# schematics.net
KiCad netlist of a schematic drawn in EasyEDA
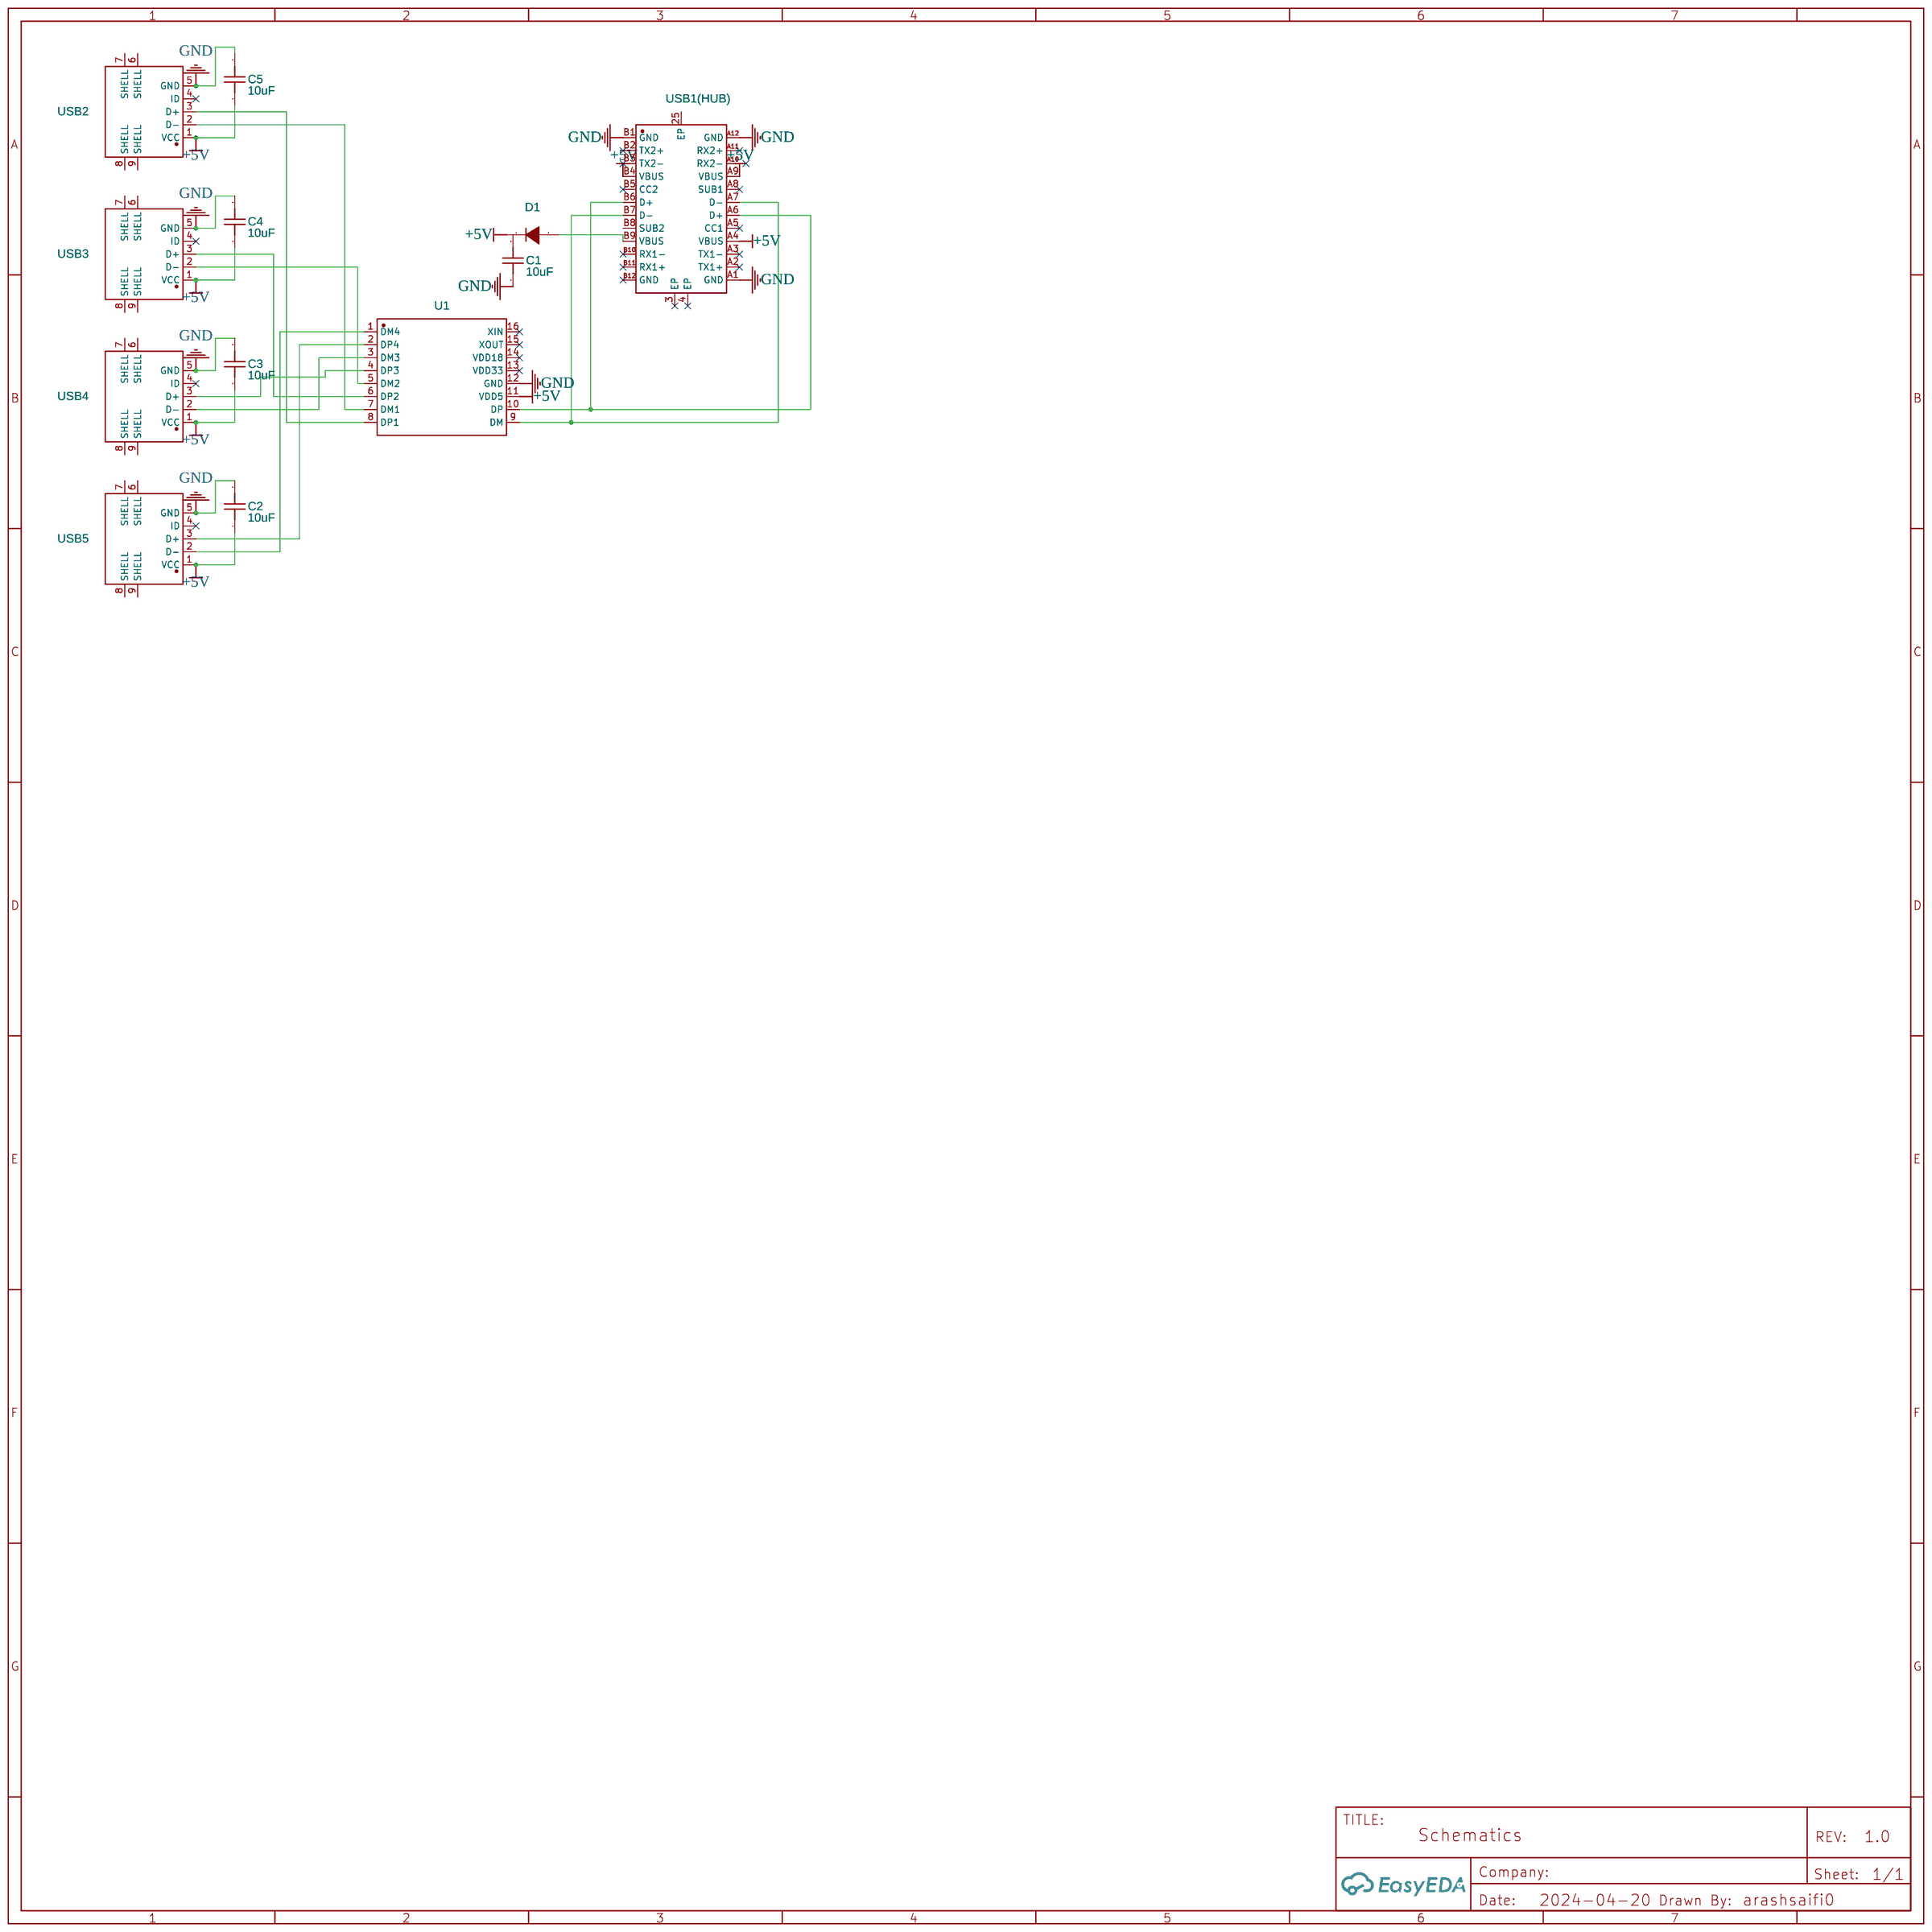
[diagram p0: schematic sheet]

(export (version "E")
  (design (tool "Eeschema 10.0.6"))
  (components
    (comp (ref "C1")
      (value "10uF")
      (fields
        (field (name "Manufacturer Part") "CL10A106KP8NNNC")
        (field (name "Manufacturer") "SAMSUNG(三星)")
      )
      (libsource (lib "") (part "CL10A106KP8NNNC"))
    )
    (comp (ref "C2")
      (value "10uF")
      (fields
        (field (name "Manufacturer Part") "CL10A106KP8NNNC")
        (field (name "Manufacturer") "SAMSUNG(三星)")
      )
      (libsource (lib "") (part "CL10A106KP8NNNC"))
    )
    (comp (ref "C3")
      (value "10uF")
      (fields
        (field (name "Manufacturer Part") "CL10A106KP8NNNC")
        (field (name "Manufacturer") "SAMSUNG(三星)")
      )
      (libsource (lib "") (part "CL10A106KP8NNNC"))
    )
    (comp (ref "C4")
      (value "10uF")
      (fields
        (field (name "Manufacturer Part") "CL10A106KP8NNNC")
        (field (name "Manufacturer") "SAMSUNG(三星)")
      )
      (libsource (lib "") (part "CL10A106KP8NNNC"))
    )
    (comp (ref "C5")
      (value "10uF")
      (fields
        (field (name "Manufacturer Part") "CL10A106KP8NNNC")
        (field (name "Manufacturer") "SAMSUNG(三星)")
      )
      (libsource (lib "") (part "CL10A106KP8NNNC"))
    )
    (comp (ref "D1")
      (value "NSR0320MW2T1G")
      (fields (field (name "Manufacturer") "onsemi(安森美)"))
      (libsource (lib "") (part "NSR0320MW2T1G"))
    )
    (comp (ref "U1")
      (value "SL2.1A")
      (fields (field (name "Manufacturer") "CoreChips(和芯润德)"))
      (libsource (lib "") (part "SL2.1A"))
    )
    (comp (ref "USB1(HUB)")
      (value "TYPE-C 24P QT")
      (fields (field (name "Manufacturer") "SHOU HAN(首韩)"))
      (libsource (lib "") (part "TYPE-C 24P QT"))
    )
    (comp (ref "USB2")
      (value "U224-051N-3GRA035")
      (fields (field (name "Manufacturer") "XKB Connectivity(中国星坤)"))
      (libsource (lib "") (part "U224-051N-3GRA035"))
    )
    (comp (ref "USB3")
      (value "U224-051N-3GRA035")
      (fields (field (name "Manufacturer") "XKB Connectivity(中国星坤)"))
      (libsource (lib "") (part "U224-051N-3GRA035"))
    )
    (comp (ref "USB4")
      (value "U224-051N-3GRA035")
      (fields (field (name "Manufacturer") "XKB Connectivity(中国星坤)"))
      (libsource (lib "") (part "U224-051N-3GRA035"))
    )
    (comp (ref "USB5")
      (value "U224-051N-3GRA035")
      (fields (field (name "Manufacturer") "XKB Connectivity(中国星坤)"))
      (libsource (lib "") (part "U224-051N-3GRA035"))
    )
  )
  (nets
    (net (code "1") (name "+5V") (class "Default")
      (node (ref "C2") (pin "1") (pinfunction "1_1") (pintype "unspecified"))
      (node (ref "C3") (pin "1") (pinfunction "1_1") (pintype "unspecified"))
      (node (ref "C4") (pin "1") (pinfunction "1_1") (pintype "unspecified"))
      (node (ref "C5") (pin "1") (pinfunction "1_1") (pintype "unspecified"))
      (node (ref "D1") (pin "1") (pinfunction "C_1") (pintype "unspecified"))
      (node (ref "U1") (pin "11") (pinfunction "VDD5_11") (pintype "unspecified"))
      (node (ref "USB1(HUB)") (pin "A4") (pinfunction "VBUS_A4") (pintype "unspecified"))
      (node (ref "USB1(HUB)") (pin "A9") (pinfunction "VBUS_A9") (pintype "unspecified"))
      (node (ref "USB1(HUB)") (pin "B4") (pinfunction "VBUS_B4") (pintype "unspecified"))
      (node (ref "USB2") (pin "1") (pinfunction "VCC_1") (pintype "unspecified"))
      (node (ref "USB3") (pin "1") (pinfunction "VCC_1") (pintype "unspecified"))
      (node (ref "USB4") (pin "1") (pinfunction "VCC_1") (pintype "unspecified"))
      (node (ref "USB5") (pin "1") (pinfunction "VCC_1") (pintype "unspecified"))
    )
    (net (code "2") (name "GND") (class "Default")
      (node (ref "C1") (pin "1") (pinfunction "1_1") (pintype "unspecified"))
      (node (ref "C2") (pin "2") (pinfunction "2_2") (pintype "unspecified"))
      (node (ref "C3") (pin "2") (pinfunction "2_2") (pintype "unspecified"))
      (node (ref "C4") (pin "2") (pinfunction "2_2") (pintype "unspecified"))
      (node (ref "C5") (pin "2") (pinfunction "2_2") (pintype "unspecified"))
      (node (ref "U1") (pin "12") (pinfunction "GND_12") (pintype "unspecified"))
      (node (ref "USB1(HUB)") (pin "A1") (pinfunction "GND_A1") (pintype "unspecified"))
      (node (ref "USB1(HUB)") (pin "A12") (pinfunction "GND_A12") (pintype "unspecified"))
      (node (ref "USB1(HUB)") (pin "B1") (pinfunction "GND_B1") (pintype "unspecified"))
      (node (ref "USB2") (pin "5") (pinfunction "GND_5") (pintype "unspecified"))
      (node (ref "USB3") (pin "5") (pinfunction "GND_5") (pintype "unspecified"))
      (node (ref "USB4") (pin "5") (pinfunction "GND_5") (pintype "unspecified"))
      (node (ref "USB5") (pin "5") (pinfunction "GND_5") (pintype "unspecified"))
    )
    (net (code "3") (name "Net-(D1-A)") (class "Default")
      (node (ref "D1") (pin "2") (pinfunction "A_2") (pintype "unspecified"))
      (node (ref "USB1(HUB)") (pin "B9") (pinfunction "VBUS_B9") (pintype "unspecified"))
    )
    (net (code "4") (name "Net-(U1-DM)") (class "Default")
      (node (ref "U1") (pin "9") (pinfunction "DM_9") (pintype "unspecified"))
      (node (ref "USB1(HUB)") (pin "A7") (pinfunction "D-_A7") (pintype "unspecified"))
      (node (ref "USB1(HUB)") (pin "B7") (pinfunction "D-_B7") (pintype "unspecified"))
    )
    (net (code "5") (name "Net-(U1-DM1)") (class "Default")
      (node (ref "U1") (pin "7") (pinfunction "DM1_7") (pintype "unspecified"))
      (node (ref "USB2") (pin "2") (pinfunction "D-_2") (pintype "unspecified"))
    )
    (net (code "6") (name "Net-(U1-DM2)") (class "Default")
      (node (ref "U1") (pin "5") (pinfunction "DM2_5") (pintype "unspecified"))
      (node (ref "USB3") (pin "2") (pinfunction "D-_2") (pintype "unspecified"))
    )
    (net (code "7") (name "Net-(U1-DM3)") (class "Default")
      (node (ref "U1") (pin "3") (pinfunction "DM3_3") (pintype "unspecified"))
      (node (ref "USB4") (pin "2") (pinfunction "D-_2") (pintype "unspecified"))
    )
    (net (code "8") (name "Net-(U1-DM4)") (class "Default")
      (node (ref "U1") (pin "1") (pinfunction "DM4_1") (pintype "unspecified"))
      (node (ref "USB5") (pin "2") (pinfunction "D-_2") (pintype "unspecified"))
    )
    (net (code "9") (name "Net-(U1-DP)") (class "Default")
      (node (ref "U1") (pin "10") (pinfunction "DP_10") (pintype "unspecified"))
      (node (ref "USB1(HUB)") (pin "A6") (pinfunction "D+_A6") (pintype "unspecified"))
      (node (ref "USB1(HUB)") (pin "B6") (pinfunction "D+_B6") (pintype "unspecified"))
    )
    (net (code "10") (name "Net-(U1-DP1)") (class "Default")
      (node (ref "U1") (pin "8") (pinfunction "DP1_8") (pintype "unspecified"))
      (node (ref "USB2") (pin "3") (pinfunction "D+_3") (pintype "unspecified"))
    )
    (net (code "11") (name "Net-(U1-DP2)") (class "Default")
      (node (ref "U1") (pin "6") (pinfunction "DP2_6") (pintype "unspecified"))
      (node (ref "USB3") (pin "3") (pinfunction "D+_3") (pintype "unspecified"))
    )
    (net (code "12") (name "Net-(U1-DP3)") (class "Default")
      (node (ref "U1") (pin "4") (pinfunction "DP3_4") (pintype "unspecified"))
      (node (ref "USB4") (pin "3") (pinfunction "D+_3") (pintype "unspecified"))
    )
    (net (code "13") (name "Net-(U1-DP4)") (class "Default")
      (node (ref "U1") (pin "2") (pinfunction "DP4_2") (pintype "unspecified"))
      (node (ref "USB5") (pin "3") (pinfunction "D+_3") (pintype "unspecified"))
    )
    (net (code "14") (name "unconnected-(C1-Pad2)") (class "Default")
      (node (ref "C1") (pin "2") (pinfunction "2_2") (pintype "unspecified"))
    )
    (net (code "15") (name "unconnected-(U1-VDD18-Pad14)") (class "Default")
      (node (ref "U1") (pin "14") (pinfunction "VDD18_14") (pintype "unspecified+no_connect"))
    )
    (net (code "16") (name "unconnected-(U1-VDD33-Pad13)") (class "Default")
      (node (ref "U1") (pin "13") (pinfunction "VDD33_13") (pintype "unspecified+no_connect"))
    )
    (net (code "17") (name "unconnected-(U1-XIN-Pad16)") (class "Default")
      (node (ref "U1") (pin "16") (pinfunction "XIN_16") (pintype "unspecified+no_connect"))
    )
    (net (code "18") (name "unconnected-(U1-XOUT-Pad15)") (class "Default")
      (node (ref "U1") (pin "15") (pinfunction "XOUT_15") (pintype "unspecified+no_connect"))
    )
    (net (code "19") (name "unconnected-(USB1(HUB)-CC1-PadA5)") (class "Default")
      (node (ref "USB1(HUB)") (pin "A5") (pinfunction "CC1_A5") (pintype "unspecified+no_connect"))
    )
    (net (code "20") (name "unconnected-(USB1(HUB)-CC2-PadB5)") (class "Default")
      (node (ref "USB1(HUB)") (pin "B5") (pinfunction "CC2_B5") (pintype "unspecified+no_connect"))
    )
    (net (code "21") (name "unconnected-(USB1(HUB)-EP-Pad3)") (class "Default")
      (node (ref "USB1(HUB)") (pin "3") (pinfunction "EP_3") (pintype "unspecified+no_connect"))
    )
    (net (code "22") (name "unconnected-(USB1(HUB)-EP-Pad4)") (class "Default")
      (node (ref "USB1(HUB)") (pin "4") (pinfunction "EP_4") (pintype "unspecified+no_connect"))
    )
    (net (code "23") (name "unconnected-(USB1(HUB)-EP-Pad25)") (class "Default")
      (node (ref "USB1(HUB)") (pin "25") (pinfunction "EP_25") (pintype "unspecified"))
    )
    (net (code "24") (name "unconnected-(USB1(HUB)-GND-PadB12)") (class "Default")
      (node (ref "USB1(HUB)") (pin "B12") (pinfunction "GND_B12") (pintype "unspecified+no_connect"))
    )
    (net (code "25") (name "unconnected-(USB1(HUB)-RX1+-PadB11)") (class "Default")
      (node (ref "USB1(HUB)") (pin "B11") (pinfunction "RX1+_B11") (pintype "unspecified+no_connect"))
    )
    (net (code "26") (name "unconnected-(USB1(HUB)-RX1--PadB10)") (class "Default")
      (node (ref "USB1(HUB)") (pin "B10") (pinfunction "RX1-_B10") (pintype "unspecified+no_connect"))
    )
    (net (code "27") (name "unconnected-(USB1(HUB)-RX2+-PadA11)") (class "Default")
      (node (ref "USB1(HUB)") (pin "A11") (pinfunction "RX2+_A11") (pintype "unspecified+no_connect"))
    )
    (net (code "28") (name "unconnected-(USB1(HUB)-RX2--PadA10)") (class "Default")
      (node (ref "USB1(HUB)") (pin "A10") (pinfunction "RX2-_A10") (pintype "unspecified"))
    )
    (net (code "29") (name "unconnected-(USB1(HUB)-SUB1-PadA8)") (class "Default")
      (node (ref "USB1(HUB)") (pin "A8") (pinfunction "SUB1_A8") (pintype "unspecified+no_connect"))
    )
    (net (code "30") (name "unconnected-(USB1(HUB)-SUB2-PadB8)") (class "Default")
      (node (ref "USB1(HUB)") (pin "B8") (pinfunction "SUB2_B8") (pintype "unspecified"))
    )
    (net (code "31") (name "unconnected-(USB1(HUB)-TX1+-PadA2)") (class "Default")
      (node (ref "USB1(HUB)") (pin "A2") (pinfunction "TX1+_A2") (pintype "unspecified+no_connect"))
    )
    (net (code "32") (name "unconnected-(USB1(HUB)-TX1--PadA3)") (class "Default")
      (node (ref "USB1(HUB)") (pin "A3") (pinfunction "TX1-_A3") (pintype "unspecified+no_connect"))
    )
    (net (code "33") (name "unconnected-(USB1(HUB)-TX2+-PadB2)") (class "Default")
      (node (ref "USB1(HUB)") (pin "B2") (pinfunction "TX2+_B2") (pintype "unspecified+no_connect"))
    )
    (net (code "34") (name "unconnected-(USB1(HUB)-TX2--PadB3)") (class "Default")
      (node (ref "USB1(HUB)") (pin "B3") (pinfunction "TX2-_B3") (pintype "unspecified+no_connect"))
    )
    (net (code "35") (name "unconnected-(USB2-ID-Pad4)") (class "Default")
      (node (ref "USB2") (pin "4") (pinfunction "ID_4") (pintype "unspecified+no_connect"))
    )
    (net (code "36") (name "unconnected-(USB2-SHELL-Pad6)") (class "Default")
      (node (ref "USB2") (pin "6") (pinfunction "SHELL_6") (pintype "unspecified"))
    )
    (net (code "37") (name "unconnected-(USB2-SHELL-Pad7)") (class "Default")
      (node (ref "USB2") (pin "7") (pinfunction "SHELL_7") (pintype "unspecified"))
    )
    (net (code "38") (name "unconnected-(USB2-SHELL-Pad8)") (class "Default")
      (node (ref "USB2") (pin "8") (pinfunction "SHELL_8") (pintype "unspecified"))
    )
    (net (code "39") (name "unconnected-(USB2-SHELL-Pad9)") (class "Default")
      (node (ref "USB2") (pin "9") (pinfunction "SHELL_9") (pintype "unspecified"))
    )
    (net (code "40") (name "unconnected-(USB3-ID-Pad4)") (class "Default")
      (node (ref "USB3") (pin "4") (pinfunction "ID_4") (pintype "unspecified+no_connect"))
    )
    (net (code "41") (name "unconnected-(USB3-SHELL-Pad6)") (class "Default")
      (node (ref "USB3") (pin "6") (pinfunction "SHELL_6") (pintype "unspecified"))
    )
    (net (code "42") (name "unconnected-(USB3-SHELL-Pad7)") (class "Default")
      (node (ref "USB3") (pin "7") (pinfunction "SHELL_7") (pintype "unspecified"))
    )
    (net (code "43") (name "unconnected-(USB3-SHELL-Pad8)") (class "Default")
      (node (ref "USB3") (pin "8") (pinfunction "SHELL_8") (pintype "unspecified"))
    )
    (net (code "44") (name "unconnected-(USB3-SHELL-Pad9)") (class "Default")
      (node (ref "USB3") (pin "9") (pinfunction "SHELL_9") (pintype "unspecified"))
    )
    (net (code "45") (name "unconnected-(USB4-ID-Pad4)") (class "Default")
      (node (ref "USB4") (pin "4") (pinfunction "ID_4") (pintype "unspecified+no_connect"))
    )
    (net (code "46") (name "unconnected-(USB4-SHELL-Pad6)") (class "Default")
      (node (ref "USB4") (pin "6") (pinfunction "SHELL_6") (pintype "unspecified"))
    )
    (net (code "47") (name "unconnected-(USB4-SHELL-Pad7)") (class "Default")
      (node (ref "USB4") (pin "7") (pinfunction "SHELL_7") (pintype "unspecified"))
    )
    (net (code "48") (name "unconnected-(USB4-SHELL-Pad8)") (class "Default")
      (node (ref "USB4") (pin "8") (pinfunction "SHELL_8") (pintype "unspecified"))
    )
    (net (code "49") (name "unconnected-(USB4-SHELL-Pad9)") (class "Default")
      (node (ref "USB4") (pin "9") (pinfunction "SHELL_9") (pintype "unspecified"))
    )
    (net (code "50") (name "unconnected-(USB5-ID-Pad4)") (class "Default")
      (node (ref "USB5") (pin "4") (pinfunction "ID_4") (pintype "unspecified+no_connect"))
    )
    (net (code "51") (name "unconnected-(USB5-SHELL-Pad6)") (class "Default")
      (node (ref "USB5") (pin "6") (pinfunction "SHELL_6") (pintype "unspecified"))
    )
    (net (code "52") (name "unconnected-(USB5-SHELL-Pad7)") (class "Default")
      (node (ref "USB5") (pin "7") (pinfunction "SHELL_7") (pintype "unspecified"))
    )
    (net (code "53") (name "unconnected-(USB5-SHELL-Pad8)") (class "Default")
      (node (ref "USB5") (pin "8") (pinfunction "SHELL_8") (pintype "unspecified"))
    )
    (net (code "54") (name "unconnected-(USB5-SHELL-Pad9)") (class "Default")
      (node (ref "USB5") (pin "9") (pinfunction "SHELL_9") (pintype "unspecified"))
    )
  )
)
